# m1.net
KiCad netlist of a schematic drawn in Altium Designer
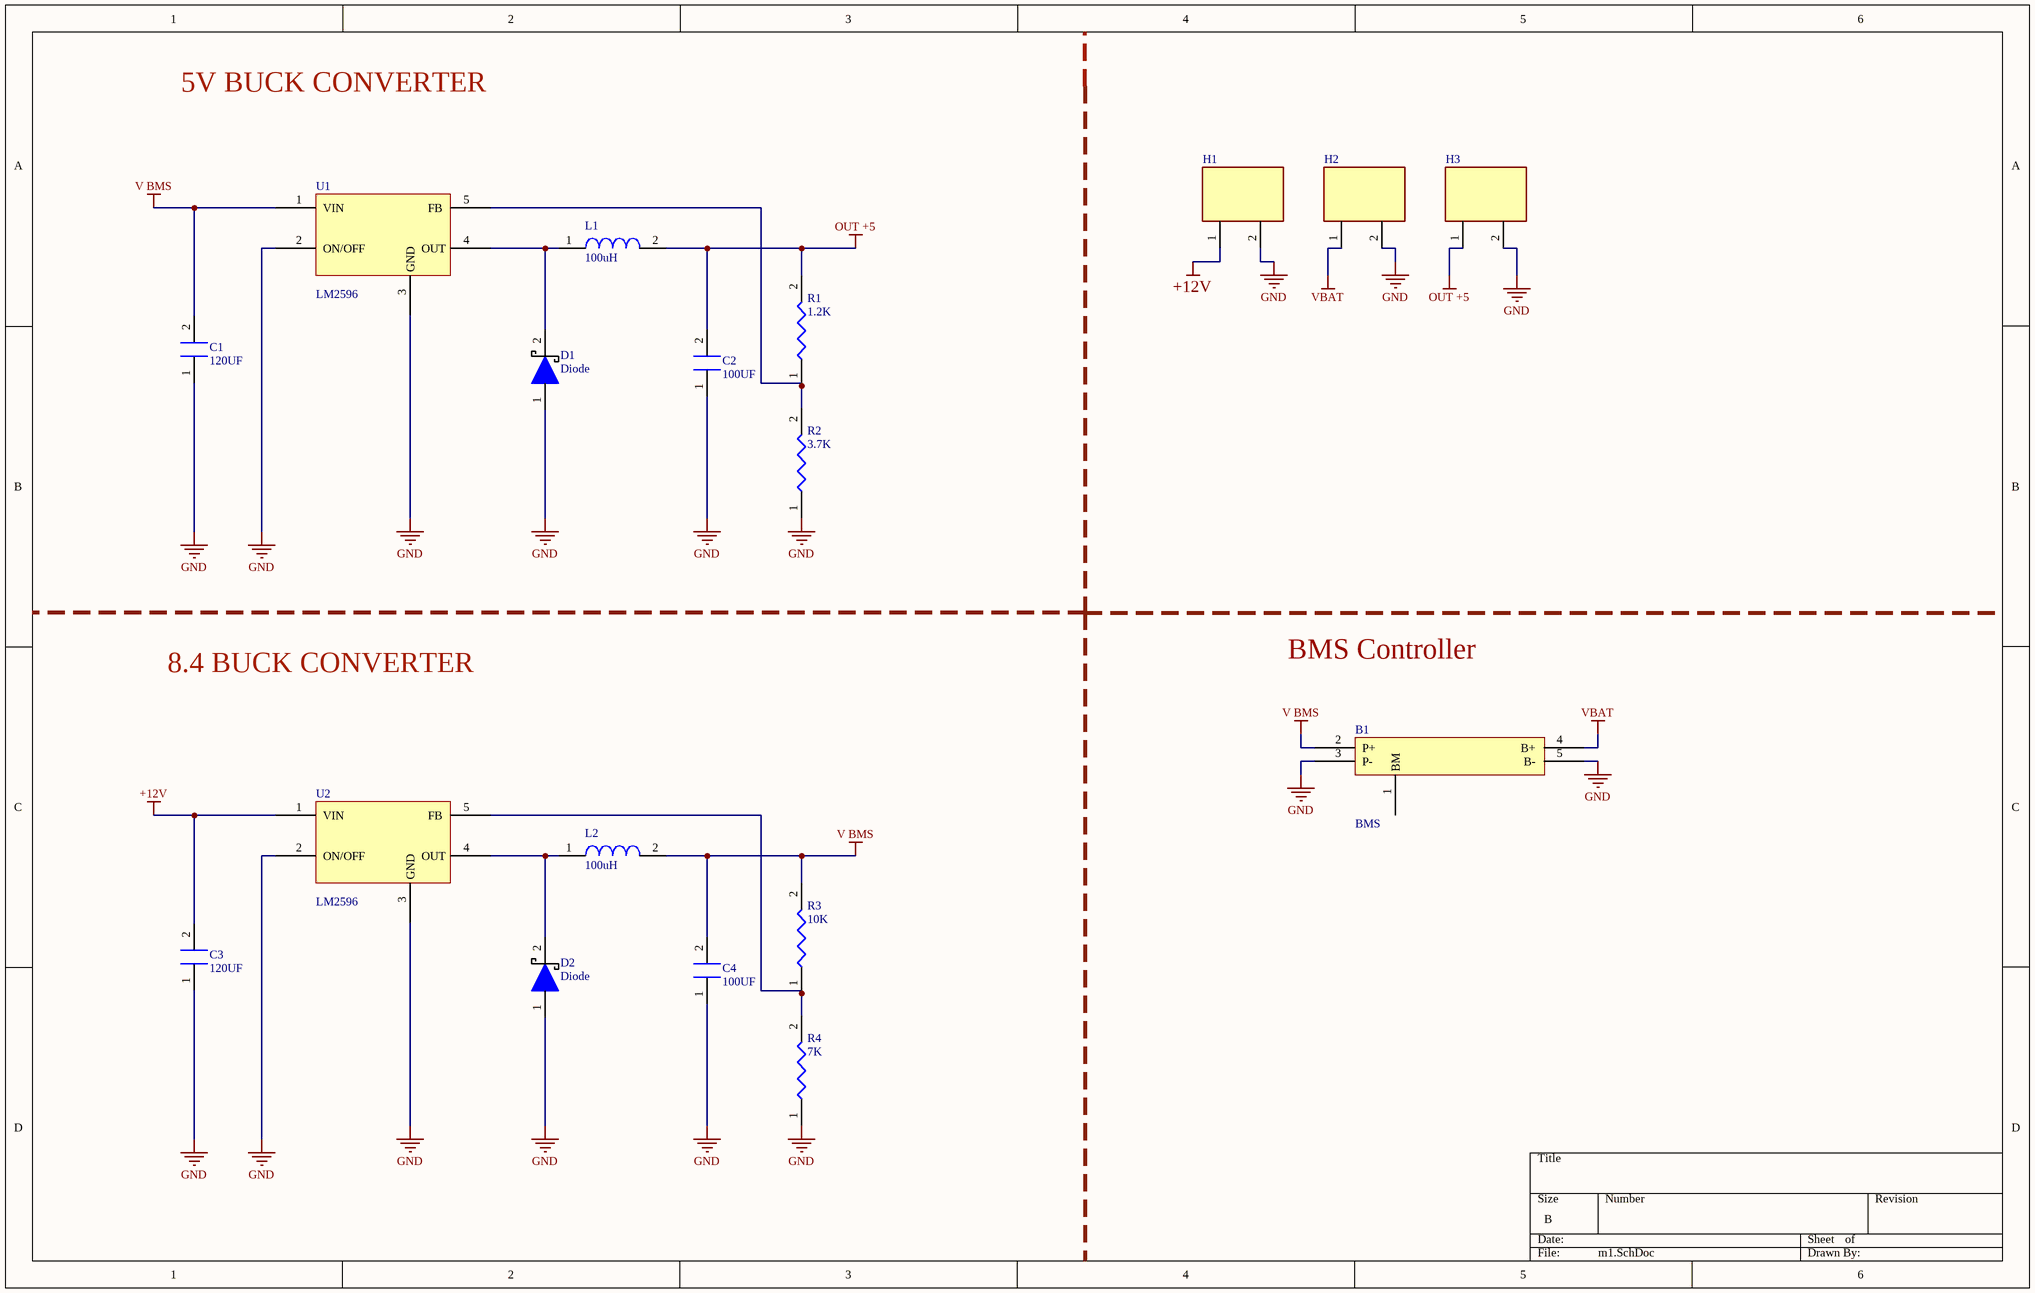
[diagram p0: m1.SchDoc]

(export (version "E")
  (design (tool "Eeschema 10.0.6"))
  (components
    (comp (ref "B1") (value "BMS") (libsource (lib "m1_Schlib1") (part "BMS")))
    (comp (ref "C1")
      (value "120UF")
      (footprint "CAPACITOR")
      (libsource (lib "m1_Schlib1") (part "Capacitor"))
    )
    (comp (ref "C2")
      (value "100UF")
      (footprint "CAPACITOR")
      (libsource (lib "m1_Schlib1") (part "Capacitor"))
    )
    (comp (ref "C3")
      (value "120UF")
      (footprint "CAPACITOR")
      (libsource (lib "m1_Schlib1") (part "Capacitor"))
    )
    (comp (ref "C4")
      (value "100UF")
      (footprint "CAPACITOR")
      (libsource (lib "m1_Schlib1") (part "Capacitor"))
    )
    (comp (ref "D1") (value "Diode") (footprint "DIODE") (libsource (lib "m1_Schlib1") (part "Diode")))
    (comp (ref "D2") (value "Diode") (footprint "DIODE") (libsource (lib "m1_Schlib1") (part "Diode")))
    (comp (ref "H1") (value "Header") (footprint "HEADER") (libsource (lib "m1_Schlib1") (part "Header")))
    (comp (ref "H2") (value "Header") (footprint "HEADER") (libsource (lib "m1_Schlib1") (part "Header")))
    (comp (ref "H3") (value "Header") (footprint "HEADER") (libsource (lib "m1_Schlib1") (part "Header")))
    (comp (ref "L1") (value "100uH") (footprint "Inductor") (libsource (lib "m1_Schlib1") (part "Inductor")))
    (comp (ref "L2") (value "100uH") (footprint "Inductor") (libsource (lib "m1_Schlib1") (part "Inductor")))
    (comp (ref "R1") (value "1.2K") (footprint "Resistor") (libsource (lib "m1_Schlib1") (part "Resistor")))
    (comp (ref "R2") (value "3.7K") (footprint "Resistor") (libsource (lib "m1_Schlib1") (part "Resistor")))
    (comp (ref "R3") (value "10K") (footprint "Resistor") (libsource (lib "m1_Schlib1") (part "Resistor")))
    (comp (ref "R4") (value "7K") (footprint "Resistor") (libsource (lib "m1_Schlib1") (part "Resistor")))
    (comp (ref "U1") (value "LM2596") (footprint "LM2595") (libsource (lib "m1_Schlib1") (part "LM2596")))
    (comp (ref "U2") (value "LM2596") (footprint "LM2595") (libsource (lib "m1_Schlib1") (part "LM2596")))
  )
  (nets
    (net (code "1") (name "+12V") (class "Default")
      (node (ref "C3") (pin "2") (pinfunction "2_2") (pintype "passive"))
      (node (ref "H1") (pin "1") (pinfunction "1_1") (pintype "passive"))
      (node (ref "U2") (pin "1") (pinfunction "VIN_1") (pintype "passive"))
    )
    (net (code "2") (name "GND") (class "Default")
      (node (ref "B1") (pin "3") (pinfunction "P-_3") (pintype "passive"))
      (node (ref "B1") (pin "5") (pinfunction "B-_5") (pintype "passive"))
      (node (ref "C1") (pin "1") (pinfunction "1_1") (pintype "passive"))
      (node (ref "C2") (pin "1") (pinfunction "1_1") (pintype "passive"))
      (node (ref "C3") (pin "1") (pinfunction "1_1") (pintype "passive"))
      (node (ref "C4") (pin "1") (pinfunction "1_1") (pintype "passive"))
      (node (ref "D1") (pin "1") (pinfunction "1_1") (pintype "passive"))
      (node (ref "D2") (pin "1") (pinfunction "1_1") (pintype "passive"))
      (node (ref "H1") (pin "2") (pinfunction "2_2") (pintype "passive"))
      (node (ref "H2") (pin "2") (pinfunction "2_2") (pintype "passive"))
      (node (ref "H3") (pin "2") (pinfunction "2_2") (pintype "passive"))
      (node (ref "R2") (pin "1") (pinfunction "1_1") (pintype "passive"))
      (node (ref "R4") (pin "1") (pinfunction "1_1") (pintype "passive"))
      (node (ref "U1") (pin "2") (pinfunction "ON/OFF_2") (pintype "passive"))
      (node (ref "U1") (pin "3") (pinfunction "GND_3") (pintype "passive"))
      (node (ref "U2") (pin "2") (pinfunction "ON/OFF_2") (pintype "passive"))
      (node (ref "U2") (pin "3") (pinfunction "GND_3") (pintype "passive"))
    )
    (net (code "3") (name "Net-(L1-13)") (class "Default")
      (node (ref "D1") (pin "2") (pinfunction "2_2") (pintype "passive"))
      (node (ref "L1") (pin "1") (pinfunction "13_1") (pintype "passive"))
      (node (ref "U1") (pin "4") (pinfunction "OUT_4") (pintype "passive"))
    )
    (net (code "4") (name "Net-(L2-13)") (class "Default")
      (node (ref "D2") (pin "2") (pinfunction "2_2") (pintype "passive"))
      (node (ref "L2") (pin "1") (pinfunction "13_1") (pintype "passive"))
      (node (ref "U2") (pin "4") (pinfunction "OUT_4") (pintype "passive"))
    )
    (net (code "5") (name "Net-(U1-FB)") (class "Default")
      (node (ref "R1") (pin "1") (pinfunction "1_1") (pintype "passive"))
      (node (ref "R2") (pin "2") (pinfunction "2_2") (pintype "passive"))
      (node (ref "U1") (pin "5") (pinfunction "FB_5") (pintype "passive"))
    )
    (net (code "6") (name "Net-(U2-FB)") (class "Default")
      (node (ref "R3") (pin "1") (pinfunction "1_1") (pintype "passive"))
      (node (ref "R4") (pin "2") (pinfunction "2_2") (pintype "passive"))
      (node (ref "U2") (pin "5") (pinfunction "FB_5") (pintype "passive"))
    )
    (net (code "7") (name "OUT +5") (class "Default")
      (node (ref "C2") (pin "2") (pinfunction "2_2") (pintype "passive"))
      (node (ref "H3") (pin "1") (pinfunction "1_1") (pintype "passive"))
      (node (ref "L1") (pin "2") (pinfunction "14_2") (pintype "passive"))
      (node (ref "R1") (pin "2") (pinfunction "2_2") (pintype "passive"))
    )
    (net (code "8") (name "V BMS") (class "Default")
      (node (ref "B1") (pin "2") (pinfunction "P+_2") (pintype "passive"))
      (node (ref "C1") (pin "2") (pinfunction "2_2") (pintype "passive"))
      (node (ref "C4") (pin "2") (pinfunction "2_2") (pintype "passive"))
      (node (ref "L2") (pin "2") (pinfunction "14_2") (pintype "passive"))
      (node (ref "R3") (pin "2") (pinfunction "2_2") (pintype "passive"))
      (node (ref "U1") (pin "1") (pinfunction "VIN_1") (pintype "passive"))
    )
    (net (code "9") (name "VBAT") (class "Default")
      (node (ref "B1") (pin "4") (pinfunction "B+_4") (pintype "passive"))
      (node (ref "H2") (pin "1") (pinfunction "1_1") (pintype "passive"))
    )
    (net (code "10") (name "unconnected-(B1-BM-Pad1)") (class "Default")
      (node (ref "B1") (pin "1") (pinfunction "BM_1") (pintype "passive"))
    )
  )
)
